# RP2040.net
KiCad netlist of a schematic drawn in Altium Designer
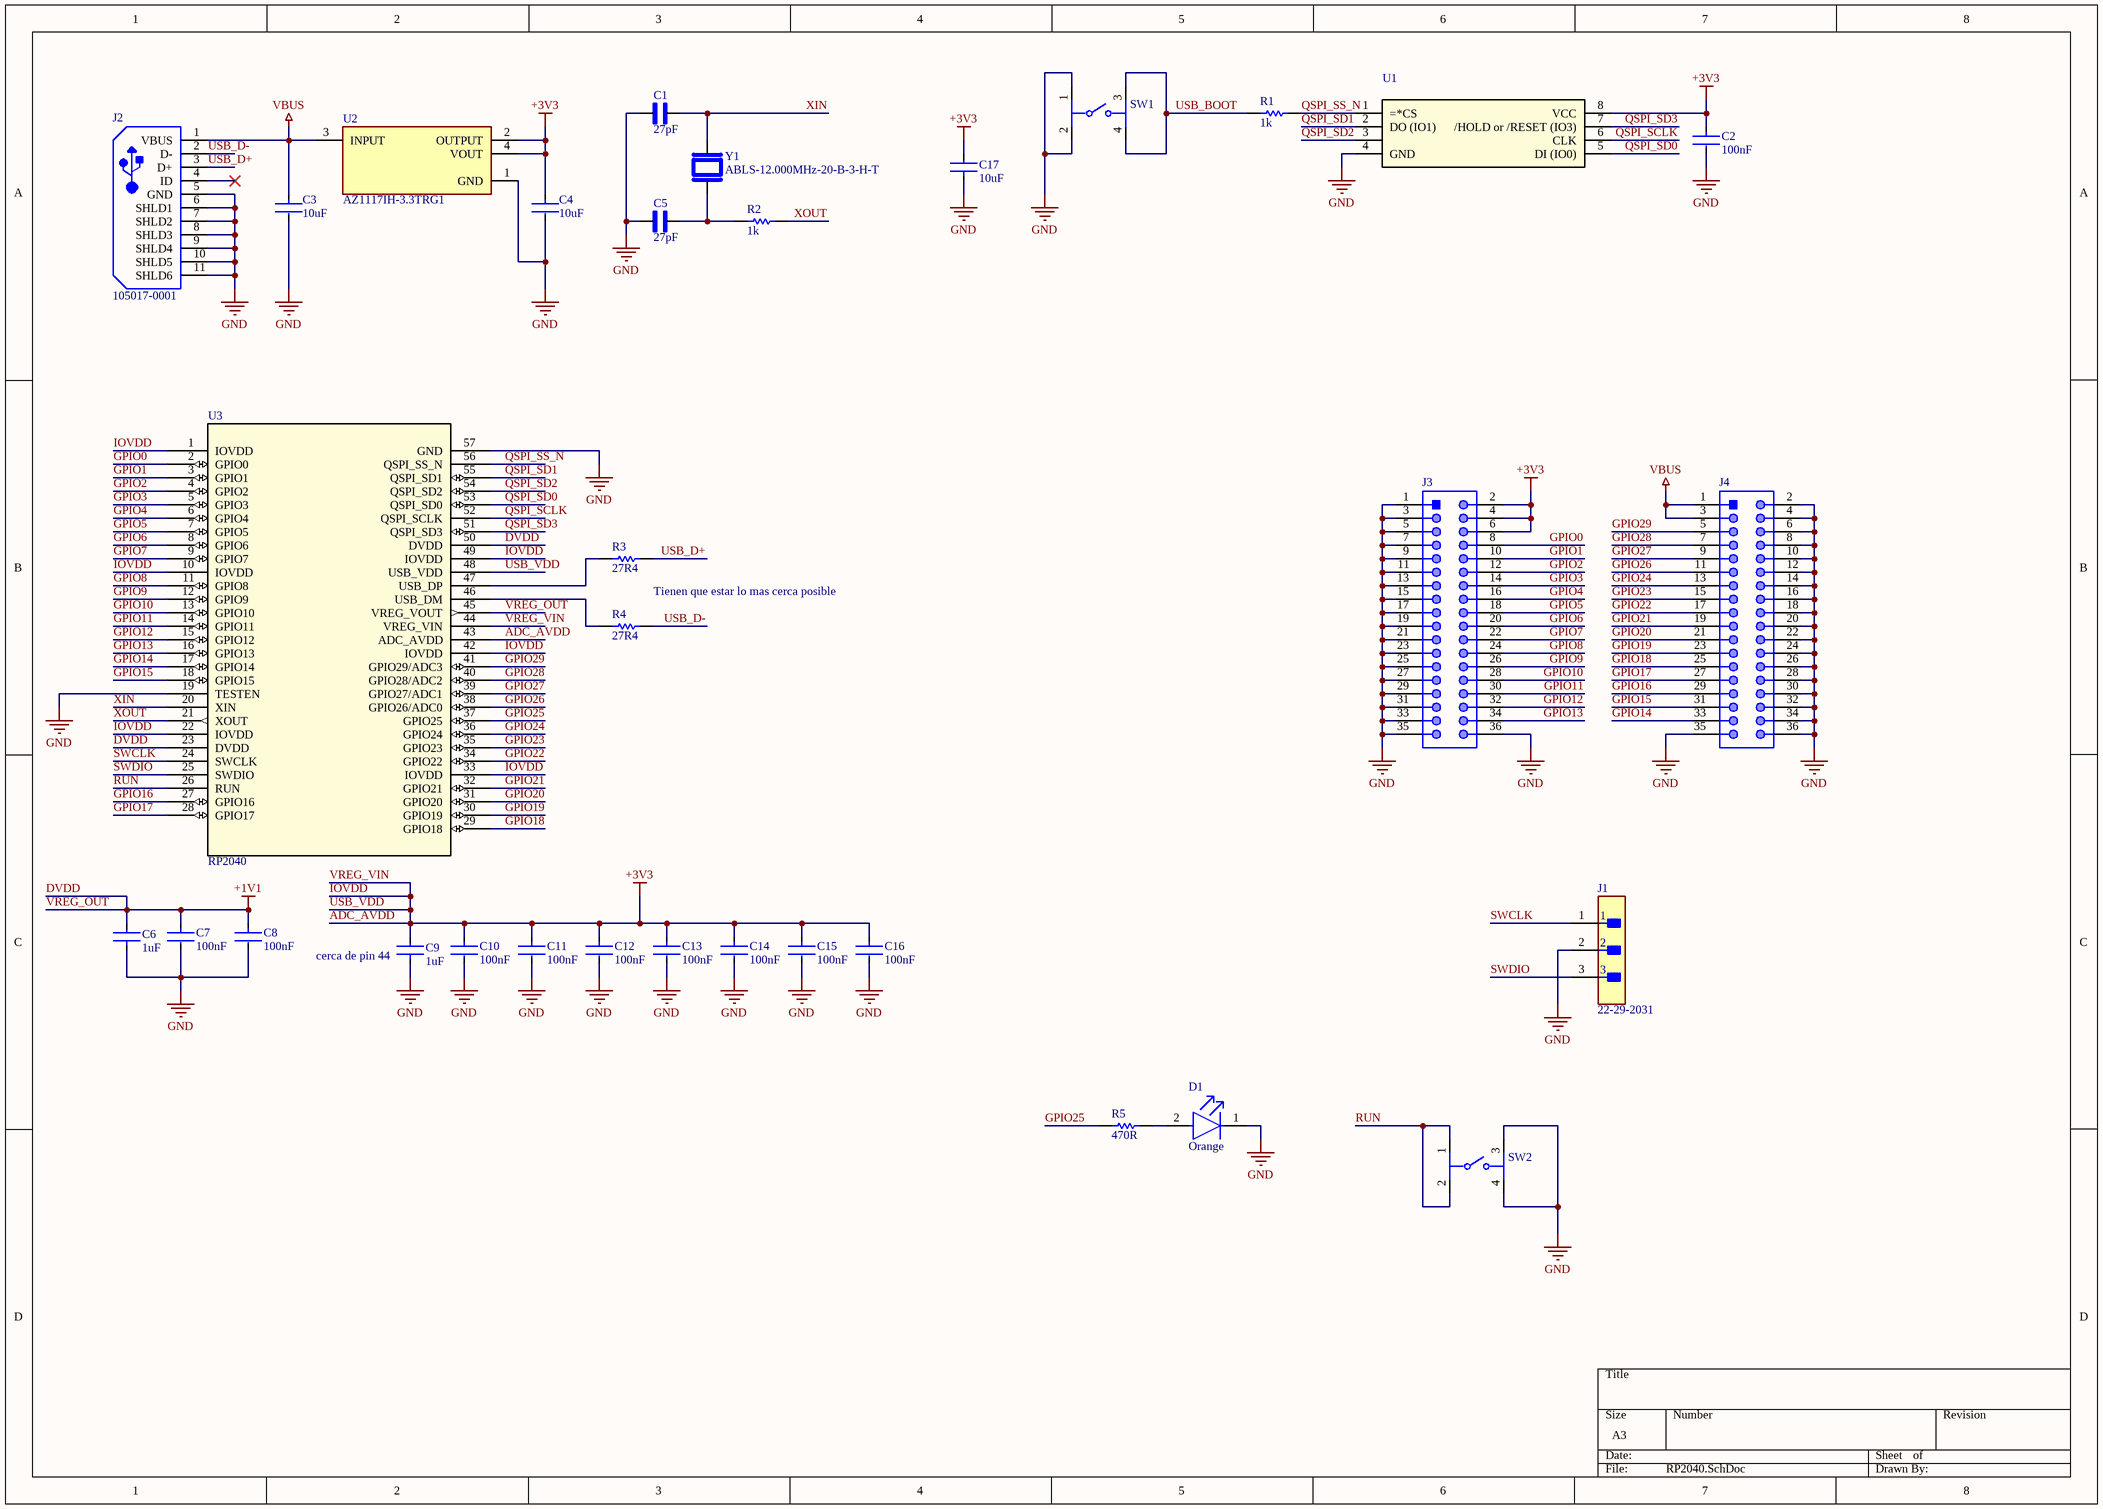
[diagram p0: RP2040.SchDoc]

(export (version "E")
  (design (tool "Eeschema 10.0.6"))
  (components
    (comp (ref "C1")
      (value "CL21C270JCANNNC")
      (footprint "CAPC2012X140N")
      (description "CL21 Series 27 pF 100 V ±5 % Tolerance C0G SMT Multilayer Ceramic Capacitor")
      (fields
        (field (name "MANUFACTURER") "Samsung")
        (field (name "TOLERANCE") "5%")
        (field (name "CAPACITANCE") "27pF")
      )
      (libsource (lib "CL21C270JCANNNC") (part "CL21C270JCANNNC"))
    )
    (comp (ref "C2")
      (value "CL21B104KBCNNNC")
      (footprint "FP-CL21-IPC_C")
      (description "CL21 Series 0805 100nF 50V ±10% Tolerance X7R Multilayer Ceramic Chip Capacitor")
      (fields
        (field (name "TOLERANCE") "10%")
        (field (name "CAPACITANCE") "100nF")
        (field (name "VOLTAGE") "50V")
      )
      (libsource (lib "Altium Content Vault") (part "b4654b650e69147ec39a6b967a45e02"))
    )
    (comp (ref "C3")
      (value "GRM21BR61C106KE15K")
      (footprint "FP-GRM21B-0_1-IPC_A")
      (description "Chip Multilayer Ceramic Capacitors for General Purpose, 0805, 10uF, X5R, 15%, 10%, 16V")
      (fields
        (field (name "TOLERANCE") "10%")
        (field (name "VOLTAGE") "16V")
        (field (name "CAPACITANCE") "10uF")
      )
      (libsource (lib "Altium Content Vault") (part "b4654b650e69147ec39a6b967a45e02"))
    )
    (comp (ref "C4")
      (value "GRM21BR61C106KE15K")
      (footprint "FP-GRM21B-0_1-IPC_A")
      (description "Chip Multilayer Ceramic Capacitors for General Purpose, 0805, 10uF, X5R, 15%, 10%, 16V")
      (fields
        (field (name "TOLERANCE") "10%")
        (field (name "VOLTAGE") "16V")
        (field (name "CAPACITANCE") "10uF")
      )
      (libsource (lib "Altium Content Vault") (part "b4654b650e69147ec39a6b967a45e02"))
    )
    (comp (ref "C5")
      (value "CL21C270JCANNNC")
      (footprint "CAPC2012X140N")
      (description "CL21 Series 27 pF 100 V ±5 % Tolerance C0G SMT Multilayer Ceramic Capacitor")
      (fields
        (field (name "MANUFACTURER") "Samsung")
        (field (name "TOLERANCE") "5%")
        (field (name "CAPACITANCE") "27pF")
      )
      (libsource (lib "CL21C270JCANNNC") (part "CL21C270JCANNNC"))
    )
    (comp (ref "C6")
      (value "CL21B105KOFNNNE")
      (footprint "FP-CL21-IPC_A")
      (description "CL21 Series 0805 1uF 16V ±10% Tolerance X7R Multilayer Ceramic Chip Capacitor")
      (fields
        (field (name "CAPACITANCE") "1uF")
        (field (name "TOLERANCE") "10%")
        (field (name "VOLTAGE") "16V")
      )
      (libsource (lib "Altium Content Vault") (part "b4654b650e69147ec39a6b967a45e02"))
    )
    (comp (ref "C7")
      (value "CL21B104KBCNNNC")
      (footprint "FP-CL21-IPC_A")
      (description "CL21 Series 0805 100nF 50V ±10% Tolerance X7R Multilayer Ceramic Chip Capacitor")
      (fields
        (field (name "TOLERANCE") "10%")
        (field (name "CAPACITANCE") "100nF")
        (field (name "VOLTAGE") "50V")
      )
      (libsource (lib "Altium Content Vault") (part "b4654b650e69147ec39a6b967a45e02"))
    )
    (comp (ref "C8")
      (value "CL21B104KBCNNNC")
      (footprint "FP-CL21-IPC_A")
      (description "CL21 Series 0805 100nF 50V ±10% Tolerance X7R Multilayer Ceramic Chip Capacitor")
      (fields
        (field (name "TOLERANCE") "10%")
        (field (name "CAPACITANCE") "100nF")
        (field (name "VOLTAGE") "50V")
      )
      (libsource (lib "Altium Content Vault") (part "b4654b650e69147ec39a6b967a45e02"))
    )
    (comp (ref "C9")
      (value "CL21B105KOFNNNE")
      (footprint "FP-CL21-IPC_A")
      (description "CL21 Series 0805 1uF 16V ±10% Tolerance X7R Multilayer Ceramic Chip Capacitor")
      (fields
        (field (name "CAPACITANCE") "1uF")
        (field (name "TOLERANCE") "10%")
        (field (name "VOLTAGE") "16V")
      )
      (libsource (lib "Altium Content Vault") (part "b4654b650e69147ec39a6b967a45e02"))
    )
    (comp (ref "C10")
      (value "CL21B104KBCNNNC")
      (footprint "FP-CL21-IPC_A")
      (description "CL21 Series 0805 100nF 50V ±10% Tolerance X7R Multilayer Ceramic Chip Capacitor")
      (fields
        (field (name "TOLERANCE") "10%")
        (field (name "CAPACITANCE") "100nF")
        (field (name "VOLTAGE") "50V")
      )
      (libsource (lib "Altium Content Vault") (part "b4654b650e69147ec39a6b967a45e02"))
    )
    (comp (ref "C11")
      (value "CL21B104KBCNNNC")
      (footprint "FP-CL21-IPC_A")
      (description "CL21 Series 0805 100nF 50V ±10% Tolerance X7R Multilayer Ceramic Chip Capacitor")
      (fields
        (field (name "TOLERANCE") "10%")
        (field (name "CAPACITANCE") "100nF")
        (field (name "VOLTAGE") "50V")
      )
      (libsource (lib "Altium Content Vault") (part "b4654b650e69147ec39a6b967a45e02"))
    )
    (comp (ref "C12")
      (value "CL21B104KBCNNNC")
      (footprint "FP-CL21-IPC_A")
      (description "CL21 Series 0805 100nF 50V ±10% Tolerance X7R Multilayer Ceramic Chip Capacitor")
      (fields
        (field (name "TOLERANCE") "10%")
        (field (name "CAPACITANCE") "100nF")
        (field (name "VOLTAGE") "50V")
      )
      (libsource (lib "Altium Content Vault") (part "b4654b650e69147ec39a6b967a45e02"))
    )
    (comp (ref "C13")
      (value "CL21B104KBCNNNC")
      (footprint "FP-CL21-IPC_A")
      (description "CL21 Series 0805 100nF 50V ±10% Tolerance X7R Multilayer Ceramic Chip Capacitor")
      (fields
        (field (name "TOLERANCE") "10%")
        (field (name "CAPACITANCE") "100nF")
        (field (name "VOLTAGE") "50V")
      )
      (libsource (lib "Altium Content Vault") (part "b4654b650e69147ec39a6b967a45e02"))
    )
    (comp (ref "C14")
      (value "CL21B104KBCNNNC")
      (footprint "FP-CL21-IPC_A")
      (description "CL21 Series 0805 100nF 50V ±10% Tolerance X7R Multilayer Ceramic Chip Capacitor")
      (fields
        (field (name "TOLERANCE") "10%")
        (field (name "CAPACITANCE") "100nF")
        (field (name "VOLTAGE") "50V")
      )
      (libsource (lib "Altium Content Vault") (part "b4654b650e69147ec39a6b967a45e02"))
    )
    (comp (ref "C15")
      (value "CL21B104KBCNNNC")
      (footprint "FP-CL21-IPC_A")
      (description "CL21 Series 0805 100nF 50V ±10% Tolerance X7R Multilayer Ceramic Chip Capacitor")
      (fields
        (field (name "TOLERANCE") "10%")
        (field (name "CAPACITANCE") "100nF")
        (field (name "VOLTAGE") "50V")
      )
      (libsource (lib "Altium Content Vault") (part "b4654b650e69147ec39a6b967a45e02"))
    )
    (comp (ref "C16")
      (value "CL21B104KBCNNNC")
      (footprint "FP-CL21-IPC_A")
      (description "CL21 Series 0805 100nF 50V ±10% Tolerance X7R Multilayer Ceramic Chip Capacitor")
      (fields
        (field (name "TOLERANCE") "10%")
        (field (name "CAPACITANCE") "100nF")
        (field (name "VOLTAGE") "50V")
      )
      (libsource (lib "Altium Content Vault") (part "b4654b650e69147ec39a6b967a45e02"))
    )
    (comp (ref "C17")
      (value "GRM21BR61C106KE15K")
      (footprint "FP-GRM21B-0_1-IPC_A")
      (description "Chip Multilayer Ceramic Capacitors for General Purpose, 0805, 10uF, X5R, 15%, 10%, 16V")
      (fields
        (field (name "TOLERANCE") "10%")
        (field (name "VOLTAGE") "16V")
        (field (name "CAPACITANCE") "10uF")
      )
      (libsource (lib "Altium Content Vault") (part "b4654b650e69147ec39a6b967a45e02"))
    )
    (comp (ref "D1")
      (value "APTR3216SECK")
      (footprint "FP-APTR3216SECK-MFG")
      (description "LED ORANGE CLEAR CHIP SMD")
      (fields (field (name "ILLUMINATION COLOR") "Orange") (field (name "MANUFACTURER") "Kingbright"))
      (libsource (lib "Altium Content Vault") (part "8706943c75ba83719d021d2fdc84c58"))
    )
    (comp (ref "J1")
      (value "22-29-2031")
      (footprint "FP-22-29-2031-MFG")
      (description "CONN HEADER VERT 3POS 2.54MM")
      (libsource (lib "Altium Content Vault") (part "0d3f023dd272f625e17a2be33dea85f"))
    )
    (comp (ref "J2")
      (value "105017-0001")
      (footprint "USB-MICRO-B_V")
      (fields (field (name "MANUFACTURER") "Molex") (field (name "MANUFACTURER PART NUMBER") "1050170001"))
      (libsource (lib "Altium Content Vault") (part "USB-5-6SHLD"))
    )
    (comp (ref "J3")
      (value "61303621121")
      (footprint "61303621121")
      (description "THT Vertical Pin Header WR-PHD, Pitch 2.54 mm, Dual Row, 36 pins")
      (fields (field (name "MANUFACTURER") "Wurth Elektronik") (field (name "PUBLISHER") "WurthElektronik"))
      (libsource (lib "Altium Content Vault") (part "WE-CN-2P-M-R36"))
    )
    (comp (ref "J4")
      (value "61303621121")
      (footprint "61303621121")
      (description "THT Vertical Pin Header WR-PHD, Pitch 2.54 mm, Dual Row, 36 pins")
      (fields (field (name "MANUFACTURER") "Wurth Elektronik") (field (name "PUBLISHER") "WurthElektronik"))
      (libsource (lib "Altium Content Vault") (part "WE-CN-2P-M-R36"))
    )
    (comp (ref "R1")
      (value "RC0805JR-131KL")
      (footprint "RESC2013X60X35ML10T20")
      (description "Res Thick Film 0805 1K Ohm 5% 0.125W(1/8W) ±100ppm/C Pad SMD T/R")
      (fields
        (field (name "MANUFACTURER") "Yageo")
        (field (name "RESISTANCE") "1k")
        (field (name "TOLERANCE") "5%")
      )
      (libsource (lib "Altium Content Vault") (part "RES"))
    )
    (comp (ref "R2")
      (value "RC0805JR-131KL")
      (footprint "RESC2013X60X35ML10T20")
      (fields
        (field (name "MANUFACTURER") "Yageo")
        (field (name "RESISTANCE") "1k")
        (field (name "TOLERANCE") "5%")
      )
      (libsource (lib "Altium Content Vault") (part "RES"))
    )
    (comp (ref "R3")
      (value "RK73H2ATTD27R4F")
      (footprint "RESC2013X60X30NL20T20")
      (description "Res Thick Film 0805 27.4 Ohm 1% 0.25W(1/4W) ±100ppm/C Pad SMD Automotive T/R")
      (fields
        (field (name "MANUFACTURER") "KOA Speer")
        (field (name "RESISTANCE") "27R4")
        (field (name "TOLERANCE") "1%")
      )
      (libsource (lib "Altium Content Vault") (part "RES"))
    )
    (comp (ref "R4")
      (value "RK73H2ATTD27R4F")
      (footprint "RESC2013X60X30NL20T20")
      (description "Res Thick Film 0805 27.4 Ohm 1% 0.25W(1/4W) ±100ppm/C Pad SMD Automotive T/R")
      (fields
        (field (name "MANUFACTURER") "KOA Speer")
        (field (name "RESISTANCE") "27R4")
        (field (name "TOLERANCE") "1%")
      )
      (libsource (lib "Altium Content Vault") (part "RES"))
    )
    (comp (ref "R5")
      (value "RC0805FR-07470RL")
      (footprint "RESC2013X60X35LL10T20")
      (description "Chip Resistor, 470 Ohm, +/- 1%, 125 mW, -55 to 155 degC, 0805 (2012 Metric), RoHS, Tape and Reel")
      (fields
        (field (name "MANUFACTURER") "Yageo")
        (field (name "RESISTANCE") "470R")
        (field (name "TOLERANCE") "1%")
      )
      (libsource (lib "Altium Content Vault") (part "RES-2"))
    )
    (comp (ref "SW1")
      (value "PTS526SK15SMTR2LFS")
      (footprint "FP-PTS526SK15SMTR2LFS-MFG")
      (description "TACT 5.2 X 5.2, 1.5 MM H, 260GF,")
      (fields
        (field (name "MANUFACTURER") "C&K")
        (field (name "OCTOPART") "https://octopart.com/pts526+sk15+smtr2+lfs-c%26k+components-100617999")
      )
      (libsource (lib "Altium Content Vault") (part "b8895f3f4cefb76e1819d2863dba89b"))
    )
    (comp (ref "SW2")
      (value "PTS526SK15SMTR2LFS")
      (footprint "FP-PTS526SK15SMTR2LFS-MFG")
      (description "TACT 5.2 X 5.2, 1.5 MM H, 260GF,")
      (fields
        (field (name "MANUFACTURER") "C&K")
        (field (name "OCTOPART") "https://octopart.com/pts526+sk15+smtr2+lfs-c%26k+components-100617999")
      )
      (libsource (lib "Altium Content Vault") (part "b8895f3f4cefb76e1819d2863dba89b"))
    )
    (comp (ref "U1")
      (value "W25Q128JVSIQ")
      (footprint "W25Q128JVSIQ")
      (description "NOR Flash Serial (SPI, Dual SPI, Quad SPI) 3.3V 128M-bit 16M x 8 6ns 8-Pin SOIC Tube")
      (fields
        (field (name "MANUFACTURER") "Winbond")
        (field (name "COPYRIGHT") "Copyright (C) 2022 Ultra Librarian. All rights reserved.")
      )
      (libsource (lib "W25Q128JVSIQ") (part "W25Q128JVSIQ"))
    )
    (comp (ref "U2")
      (value "AZ1117IH-3.3TRG1")
      (footprint "FP-SOT223-IPC_B")
      (description "Linear Voltage Regulator IC Positive Fixed 1 Output 3.3V 800mA SOT-223")
      (fields (field (name "MANUFACTURER") "Diodes"))
      (libsource (lib "Altium Content Vault") (part "3c8a0cc3f7d1fafcf032f21e1bb5f65"))
    )
    (comp (ref "U3")
      (value "RP2040")
      (footprint "RP2040")
      (description "ARM® Cortex®-M0+ - Microcontroller IC 32-Bit Dual-Core 133MHz External Program Memory 56-QFN (7x7)")
      (fields
        (field (name "MANUFACTURER") "Raspberry Pi")
        (field (name "MANUFACTURER PART NUMBER") "SC0914(13)")
      )
      (libsource (lib "RP2040") (part "RP2040"))
    )
    (comp (ref "Y1")
      (value "ABLS-12.000MHz-20-B-3-H-T")
      (footprint "XTAL_ABLS-12.000MHz-20-B-3-H-T")
      (description "Crystal 12MHz ±25ppm (Tol) ±35ppm (Stability) 20pF FUND 50Ohm 2-Pin HC-49/US SMD T/R")
      (fields (field (name "MF") "Abracon LLC") (field (name "DIGI-KEY_PART_NUMBER") "535-15006-2-ND"))
      (libsource (lib "ABLS-12.000MHz-20-B-3-H-T") (part "ABLS-12.000MHz-20-B-3-H-T"))
    )
  )
  (nets
    (net (code "1") (name "+1V1") (class "Default")
      (node (ref "C6") (pin "2") (pinfunction "2_2") (pintype "passive"))
      (node (ref "C7") (pin "1") (pinfunction "1_1") (pintype "passive"))
      (node (ref "C8") (pin "1") (pinfunction "1_1") (pintype "passive"))
      (node (ref "U3") (pin "23") (pinfunction "DVDD_23") (pintype "power_in"))
      (node (ref "U3") (pin "45") (pinfunction "VREG_VOUT_45") (pintype "output"))
      (node (ref "U3") (pin "50") (pinfunction "DVDD_50") (pintype "power_in"))
    )
    (net (code "2") (name "+3V3") (class "Default")
      (node (ref "C10") (pin "1") (pinfunction "1_1") (pintype "passive"))
      (node (ref "C11") (pin "1") (pinfunction "1_1") (pintype "passive"))
      (node (ref "C12") (pin "1") (pinfunction "1_1") (pintype "passive"))
      (node (ref "C13") (pin "1") (pinfunction "1_1") (pintype "passive"))
      (node (ref "C14") (pin "1") (pinfunction "1_1") (pintype "passive"))
      (node (ref "C15") (pin "1") (pinfunction "1_1") (pintype "passive"))
      (node (ref "C16") (pin "1") (pinfunction "1_1") (pintype "passive"))
      (node (ref "C17") (pin "2") (pinfunction "2_2") (pintype "passive"))
      (node (ref "C2") (pin "1") (pinfunction "1_1") (pintype "passive"))
      (node (ref "C4") (pin "1") (pinfunction "1_1") (pintype "passive"))
      (node (ref "C9") (pin "2") (pinfunction "2_2") (pintype "passive"))
      (node (ref "J3") (pin "2") (pinfunction "2_2") (pintype "passive"))
      (node (ref "J3") (pin "4") (pinfunction "4_4") (pintype "passive"))
      (node (ref "J3") (pin "6") (pinfunction "6_6") (pintype "passive"))
      (node (ref "U1") (pin "8") (pinfunction "VCC_8") (pintype "power_in"))
      (node (ref "U2") (pin "2") (pinfunction "OUTPUT_2") (pintype "power_in"))
      (node (ref "U2") (pin "4") (pinfunction "VOUT_4") (pintype "power_in"))
      (node (ref "U3") (pin "1") (pinfunction "IOVDD_1") (pintype "power_in"))
      (node (ref "U3") (pin "10") (pinfunction "IOVDD_10") (pintype "power_in"))
      (node (ref "U3") (pin "22") (pinfunction "IOVDD_22") (pintype "power_in"))
      (node (ref "U3") (pin "33") (pinfunction "IOVDD_33") (pintype "power_in"))
      (node (ref "U3") (pin "42") (pinfunction "IOVDD_42") (pintype "power_in"))
      (node (ref "U3") (pin "43") (pinfunction "ADC_AVDD_43") (pintype "power_in"))
      (node (ref "U3") (pin "44") (pinfunction "VREG_VIN_44") (pintype "passive"))
      (node (ref "U3") (pin "48") (pinfunction "USB_VDD_48") (pintype "power_in"))
      (node (ref "U3") (pin "49") (pinfunction "IOVDD_49") (pintype "power_in"))
    )
    (net (code "3") (name "/GPIO0") (class "Default")
      (node (ref "J3") (pin "8") (pinfunction "8_8") (pintype "passive"))
      (node (ref "U3") (pin "2") (pinfunction "GPIO0_2") (pintype "bidirectional"))
    )
    (net (code "4") (name "/GPIO1") (class "Default")
      (node (ref "J3") (pin "10") (pinfunction "10_10") (pintype "passive"))
      (node (ref "U3") (pin "3") (pinfunction "GPIO1_3") (pintype "bidirectional"))
    )
    (net (code "5") (name "/GPIO2") (class "Default")
      (node (ref "J3") (pin "12") (pinfunction "12_12") (pintype "passive"))
      (node (ref "U3") (pin "4") (pinfunction "GPIO2_4") (pintype "bidirectional"))
    )
    (net (code "6") (name "/GPIO3") (class "Default")
      (node (ref "J3") (pin "14") (pinfunction "14_14") (pintype "passive"))
      (node (ref "U3") (pin "5") (pinfunction "GPIO3_5") (pintype "bidirectional"))
    )
    (net (code "7") (name "/GPIO4") (class "Default")
      (node (ref "J3") (pin "16") (pinfunction "16_16") (pintype "passive"))
      (node (ref "U3") (pin "6") (pinfunction "GPIO4_6") (pintype "bidirectional"))
    )
    (net (code "8") (name "/GPIO5") (class "Default")
      (node (ref "J3") (pin "18") (pinfunction "18_18") (pintype "passive"))
      (node (ref "U3") (pin "7") (pinfunction "GPIO5_7") (pintype "bidirectional"))
    )
    (net (code "9") (name "/GPIO6") (class "Default")
      (node (ref "J3") (pin "20") (pinfunction "20_20") (pintype "passive"))
      (node (ref "U3") (pin "8") (pinfunction "GPIO6_8") (pintype "bidirectional"))
    )
    (net (code "10") (name "/GPIO7") (class "Default")
      (node (ref "J3") (pin "22") (pinfunction "22_22") (pintype "passive"))
      (node (ref "U3") (pin "9") (pinfunction "GPIO7_9") (pintype "bidirectional"))
    )
    (net (code "11") (name "/GPIO8") (class "Default")
      (node (ref "J3") (pin "24") (pinfunction "24_24") (pintype "passive"))
      (node (ref "U3") (pin "11") (pinfunction "GPIO8_11") (pintype "bidirectional"))
    )
    (net (code "12") (name "/GPIO9") (class "Default")
      (node (ref "J3") (pin "26") (pinfunction "26_26") (pintype "passive"))
      (node (ref "U3") (pin "12") (pinfunction "GPIO9_12") (pintype "bidirectional"))
    )
    (net (code "13") (name "/GPIO10") (class "Default")
      (node (ref "J3") (pin "28") (pinfunction "28_28") (pintype "passive"))
      (node (ref "U3") (pin "13") (pinfunction "GPIO10_13") (pintype "bidirectional"))
    )
    (net (code "14") (name "/GPIO11") (class "Default")
      (node (ref "J3") (pin "30") (pinfunction "30_30") (pintype "passive"))
      (node (ref "U3") (pin "14") (pinfunction "GPIO11_14") (pintype "bidirectional"))
    )
    (net (code "15") (name "/GPIO12") (class "Default")
      (node (ref "J3") (pin "32") (pinfunction "32_32") (pintype "passive"))
      (node (ref "U3") (pin "15") (pinfunction "GPIO12_15") (pintype "bidirectional"))
    )
    (net (code "16") (name "/GPIO13") (class "Default")
      (node (ref "J3") (pin "34") (pinfunction "34_34") (pintype "passive"))
      (node (ref "U3") (pin "16") (pinfunction "GPIO13_16") (pintype "bidirectional"))
    )
    (net (code "17") (name "/GPIO14") (class "Default")
      (node (ref "J4") (pin "33") (pinfunction "33_33") (pintype "passive"))
      (node (ref "U3") (pin "17") (pinfunction "GPIO14_17") (pintype "bidirectional"))
    )
    (net (code "18") (name "/GPIO15") (class "Default")
      (node (ref "J4") (pin "31") (pinfunction "31_31") (pintype "passive"))
      (node (ref "U3") (pin "18") (pinfunction "GPIO15_18") (pintype "bidirectional"))
    )
    (net (code "19") (name "/GPIO16") (class "Default")
      (node (ref "J4") (pin "29") (pinfunction "29_29") (pintype "passive"))
      (node (ref "U3") (pin "27") (pinfunction "GPIO16_27") (pintype "bidirectional"))
    )
    (net (code "20") (name "/GPIO17") (class "Default")
      (node (ref "J4") (pin "27") (pinfunction "27_27") (pintype "passive"))
      (node (ref "U3") (pin "28") (pinfunction "GPIO17_28") (pintype "bidirectional"))
    )
    (net (code "21") (name "/GPIO18") (class "Default")
      (node (ref "J4") (pin "25") (pinfunction "25_25") (pintype "passive"))
      (node (ref "U3") (pin "29") (pinfunction "GPIO18_29") (pintype "bidirectional"))
    )
    (net (code "22") (name "/GPIO19") (class "Default")
      (node (ref "J4") (pin "23") (pinfunction "23_23") (pintype "passive"))
      (node (ref "U3") (pin "30") (pinfunction "GPIO19_30") (pintype "bidirectional"))
    )
    (net (code "23") (name "/GPIO20") (class "Default")
      (node (ref "J4") (pin "21") (pinfunction "21_21") (pintype "passive"))
      (node (ref "U3") (pin "31") (pinfunction "GPIO20_31") (pintype "bidirectional"))
    )
    (net (code "24") (name "/GPIO21") (class "Default")
      (node (ref "J4") (pin "19") (pinfunction "19_19") (pintype "passive"))
      (node (ref "U3") (pin "32") (pinfunction "GPIO21_32") (pintype "bidirectional"))
    )
    (net (code "25") (name "/GPIO22") (class "Default")
      (node (ref "J4") (pin "17") (pinfunction "17_17") (pintype "passive"))
      (node (ref "U3") (pin "34") (pinfunction "GPIO22_34") (pintype "bidirectional"))
    )
    (net (code "26") (name "/GPIO23") (class "Default")
      (node (ref "J4") (pin "15") (pinfunction "15_15") (pintype "passive"))
      (node (ref "U3") (pin "35") (pinfunction "GPIO23_35") (pintype "bidirectional"))
    )
    (net (code "27") (name "/GPIO24") (class "Default")
      (node (ref "J4") (pin "13") (pinfunction "13_13") (pintype "passive"))
      (node (ref "U3") (pin "36") (pinfunction "GPIO24_36") (pintype "bidirectional"))
    )
    (net (code "28") (name "/GPIO25") (class "Default")
      (node (ref "R5") (pin "1") (pinfunction "1_1") (pintype "passive"))
      (node (ref "U3") (pin "37") (pinfunction "GPIO25_37") (pintype "bidirectional"))
    )
    (net (code "29") (name "/GPIO26") (class "Default")
      (node (ref "J4") (pin "11") (pinfunction "11_11") (pintype "passive"))
      (node (ref "U3") (pin "38") (pinfunction "GPIO26/ADC0_38") (pintype "bidirectional"))
    )
    (net (code "30") (name "/GPIO27") (class "Default")
      (node (ref "J4") (pin "9") (pinfunction "9_9") (pintype "passive"))
      (node (ref "U3") (pin "39") (pinfunction "GPIO27/ADC1_39") (pintype "bidirectional"))
    )
    (net (code "31") (name "/GPIO28") (class "Default")
      (node (ref "J4") (pin "7") (pinfunction "7_7") (pintype "passive"))
      (node (ref "U3") (pin "40") (pinfunction "GPIO28/ADC2_40") (pintype "bidirectional"))
    )
    (net (code "32") (name "/GPIO29") (class "Default")
      (node (ref "J4") (pin "5") (pinfunction "5_5") (pintype "passive"))
      (node (ref "U3") (pin "41") (pinfunction "GPIO29/ADC3_41") (pintype "bidirectional"))
    )
    (net (code "33") (name "/QSPI_SCLK") (class "Default")
      (node (ref "U1") (pin "6") (pinfunction "CLK_6") (pintype "passive"))
      (node (ref "U3") (pin "52") (pinfunction "QSPI_SCLK_52") (pintype "passive"))
    )
    (net (code "34") (name "/QSPI_SD0") (class "Default")
      (node (ref "U1") (pin "5") (pinfunction "DI_(IO0)_5") (pintype "passive"))
      (node (ref "U3") (pin "53") (pinfunction "QSPI_SD0_53") (pintype "bidirectional"))
    )
    (net (code "35") (name "/QSPI_SD1") (class "Default")
      (node (ref "U1") (pin "2") (pinfunction "DO_(IO1)_2") (pintype "passive"))
      (node (ref "U3") (pin "55") (pinfunction "QSPI_SD1_55") (pintype "bidirectional"))
    )
    (net (code "36") (name "/QSPI_SD2") (class "Default")
      (node (ref "U1") (pin "3") (pinfunction "/WP_(IO2)_3") (pintype "passive"))
      (node (ref "U3") (pin "54") (pinfunction "QSPI_SD2_54") (pintype "bidirectional"))
    )
    (net (code "37") (name "/QSPI_SD3") (class "Default")
      (node (ref "U1") (pin "7") (pinfunction "/HOLD_or_/RESET_(IO3)_7") (pintype "passive"))
      (node (ref "U3") (pin "51") (pinfunction "QSPI_SD3_51") (pintype "bidirectional"))
    )
    (net (code "38") (name "/QSPI_SS_N") (class "Default")
      (node (ref "R1") (pin "1") (pinfunction "1_1") (pintype "passive"))
      (node (ref "U1") (pin "1") (pinfunction "=*CS_1") (pintype "passive"))
      (node (ref "U3") (pin "56") (pinfunction "QSPI_SS_N_56") (pintype "passive"))
    )
    (net (code "39") (name "/RUN") (class "Default")
      (node (ref "SW2") (pin "1") (pinfunction "1_1") (pintype "passive"))
      (node (ref "SW2") (pin "2") (pinfunction "2_2") (pintype "passive"))
      (node (ref "U3") (pin "26") (pinfunction "RUN_26") (pintype "passive"))
    )
    (net (code "40") (name "/SWCLK") (class "Default")
      (node (ref "J1") (pin "1") (pinfunction "1_1") (pintype "passive"))
      (node (ref "U3") (pin "24") (pinfunction "SWCLK_24") (pintype "passive"))
    )
    (net (code "41") (name "/SWDIO") (class "Default")
      (node (ref "J1") (pin "3") (pinfunction "3_3") (pintype "passive"))
      (node (ref "U3") (pin "25") (pinfunction "SWDIO_25") (pintype "passive"))
    )
    (net (code "42") (name "/USB_BOOT") (class "Default")
      (node (ref "R1") (pin "2") (pinfunction "2_2") (pintype "passive"))
      (node (ref "SW1") (pin "3") (pinfunction "3_3") (pintype "passive"))
      (node (ref "SW1") (pin "4") (pinfunction "4_4") (pintype "passive"))
    )
    (net (code "43") (name "/USB_D+") (class "Default")
      (node (ref "J2") (pin "3") (pinfunction "D+_3") (pintype "passive"))
      (node (ref "R3") (pin "1") (pinfunction "1_1") (pintype "passive"))
    )
    (net (code "44") (name "/USB_D-") (class "Default")
      (node (ref "J2") (pin "2") (pinfunction "D-_2") (pintype "passive"))
      (node (ref "R4") (pin "1") (pinfunction "1_1") (pintype "passive"))
    )
    (net (code "45") (name "/XIN") (class "Default")
      (node (ref "C1") (pin "1") (pinfunction "1_1") (pintype "passive"))
      (node (ref "U3") (pin "20") (pinfunction "XIN_20") (pintype "passive"))
      (node (ref "Y1") (pin "2") (pinfunction "2_2") (pintype "passive"))
    )
    (net (code "46") (name "/XOUT") (class "Default")
      (node (ref "R2") (pin "1") (pinfunction "1_1") (pintype "passive"))
      (node (ref "U3") (pin "21") (pinfunction "XOUT_21") (pintype "output"))
    )
    (net (code "47") (name "GND") (class "Default")
      (node (ref "C1") (pin "2") (pinfunction "2_2") (pintype "passive"))
      (node (ref "C10") (pin "2") (pinfunction "2_2") (pintype "passive"))
      (node (ref "C11") (pin "2") (pinfunction "2_2") (pintype "passive"))
      (node (ref "C12") (pin "2") (pinfunction "2_2") (pintype "passive"))
      (node (ref "C13") (pin "2") (pinfunction "2_2") (pintype "passive"))
      (node (ref "C14") (pin "2") (pinfunction "2_2") (pintype "passive"))
      (node (ref "C15") (pin "2") (pinfunction "2_2") (pintype "passive"))
      (node (ref "C16") (pin "2") (pinfunction "2_2") (pintype "passive"))
      (node (ref "C17") (pin "1") (pinfunction "1_1") (pintype "passive"))
      (node (ref "C2") (pin "2") (pinfunction "2_2") (pintype "passive"))
      (node (ref "C3") (pin "2") (pinfunction "2_2") (pintype "passive"))
      (node (ref "C4") (pin "2") (pinfunction "2_2") (pintype "passive"))
      (node (ref "C5") (pin "2") (pinfunction "2_2") (pintype "passive"))
      (node (ref "C6") (pin "1") (pinfunction "1_1") (pintype "passive"))
      (node (ref "C7") (pin "2") (pinfunction "2_2") (pintype "passive"))
      (node (ref "C8") (pin "2") (pinfunction "2_2") (pintype "passive"))
      (node (ref "C9") (pin "1") (pinfunction "1_1") (pintype "passive"))
      (node (ref "D1") (pin "1") (pinfunction "C_1") (pintype "passive"))
      (node (ref "J1") (pin "2") (pinfunction "2_2") (pintype "passive"))
      (node (ref "J2") (pin "10") (pinfunction "SHLD5_10") (pintype "passive"))
      (node (ref "J2") (pin "11") (pinfunction "SHLD6_11") (pintype "passive"))
      (node (ref "J2") (pin "5") (pinfunction "GND_5") (pintype "passive"))
      (node (ref "J2") (pin "6") (pinfunction "SHLD1_6") (pintype "passive"))
      (node (ref "J2") (pin "7") (pinfunction "SHLD2_7") (pintype "passive"))
      (node (ref "J2") (pin "8") (pinfunction "SHLD3_8") (pintype "passive"))
      (node (ref "J2") (pin "9") (pinfunction "SHLD4_9") (pintype "passive"))
      (node (ref "J3") (pin "1") (pinfunction "1_1") (pintype "passive"))
      (node (ref "J3") (pin "11") (pinfunction "11_11") (pintype "passive"))
      (node (ref "J3") (pin "13") (pinfunction "13_13") (pintype "passive"))
      (node (ref "J3") (pin "15") (pinfunction "15_15") (pintype "passive"))
      (node (ref "J3") (pin "17") (pinfunction "17_17") (pintype "passive"))
      (node (ref "J3") (pin "19") (pinfunction "19_19") (pintype "passive"))
      (node (ref "J3") (pin "21") (pinfunction "21_21") (pintype "passive"))
      (node (ref "J3") (pin "23") (pinfunction "23_23") (pintype "passive"))
      (node (ref "J3") (pin "25") (pinfunction "25_25") (pintype "passive"))
      (node (ref "J3") (pin "27") (pinfunction "27_27") (pintype "passive"))
      (node (ref "J3") (pin "29") (pinfunction "29_29") (pintype "passive"))
      (node (ref "J3") (pin "3") (pinfunction "3_3") (pintype "passive"))
      (node (ref "J3") (pin "31") (pinfunction "31_31") (pintype "passive"))
      (node (ref "J3") (pin "33") (pinfunction "33_33") (pintype "passive"))
      (node (ref "J3") (pin "35") (pinfunction "35_35") (pintype "passive"))
      (node (ref "J3") (pin "36") (pinfunction "36_36") (pintype "passive"))
      (node (ref "J3") (pin "5") (pinfunction "5_5") (pintype "passive"))
      (node (ref "J3") (pin "7") (pinfunction "7_7") (pintype "passive"))
      (node (ref "J3") (pin "9") (pinfunction "9_9") (pintype "passive"))
      (node (ref "J4") (pin "10") (pinfunction "10_10") (pintype "passive"))
      (node (ref "J4") (pin "12") (pinfunction "12_12") (pintype "passive"))
      (node (ref "J4") (pin "14") (pinfunction "14_14") (pintype "passive"))
      (node (ref "J4") (pin "16") (pinfunction "16_16") (pintype "passive"))
      (node (ref "J4") (pin "18") (pinfunction "18_18") (pintype "passive"))
      (node (ref "J4") (pin "2") (pinfunction "2_2") (pintype "passive"))
      (node (ref "J4") (pin "20") (pinfunction "20_20") (pintype "passive"))
      (node (ref "J4") (pin "22") (pinfunction "22_22") (pintype "passive"))
      (node (ref "J4") (pin "24") (pinfunction "24_24") (pintype "passive"))
      (node (ref "J4") (pin "26") (pinfunction "26_26") (pintype "passive"))
      (node (ref "J4") (pin "28") (pinfunction "28_28") (pintype "passive"))
      (node (ref "J4") (pin "30") (pinfunction "30_30") (pintype "passive"))
      (node (ref "J4") (pin "32") (pinfunction "32_32") (pintype "passive"))
      (node (ref "J4") (pin "34") (pinfunction "34_34") (pintype "passive"))
      (node (ref "J4") (pin "35") (pinfunction "35_35") (pintype "passive"))
      (node (ref "J4") (pin "36") (pinfunction "36_36") (pintype "passive"))
      (node (ref "J4") (pin "4") (pinfunction "4_4") (pintype "passive"))
      (node (ref "J4") (pin "6") (pinfunction "6_6") (pintype "passive"))
      (node (ref "J4") (pin "8") (pinfunction "8_8") (pintype "passive"))
      (node (ref "SW1") (pin "1") (pinfunction "1_1") (pintype "passive"))
      (node (ref "SW1") (pin "2") (pinfunction "2_2") (pintype "passive"))
      (node (ref "SW2") (pin "3") (pinfunction "3_3") (pintype "passive"))
      (node (ref "SW2") (pin "4") (pinfunction "4_4") (pintype "passive"))
      (node (ref "U1") (pin "4") (pinfunction "GND_4") (pintype "passive"))
      (node (ref "U2") (pin "1") (pinfunction "GND_1") (pintype "power_in"))
      (node (ref "U3") (pin "19") (pinfunction "TESTEN_19") (pintype "passive"))
      (node (ref "U3") (pin "57") (pinfunction "GND_57") (pintype "passive"))
    )
    (net (code "48") (name "Net-(C5-Pad1)") (class "Default")
      (node (ref "C5") (pin "1") (pinfunction "1_1") (pintype "passive"))
      (node (ref "R2") (pin "2") (pinfunction "2_2") (pintype "passive"))
      (node (ref "Y1") (pin "1") (pinfunction "1_1") (pintype "passive"))
    )
    (net (code "49") (name "Net-(D1-A)") (class "Default")
      (node (ref "D1") (pin "2") (pinfunction "A_2") (pintype "passive"))
      (node (ref "R5") (pin "2") (pinfunction "2_2") (pintype "passive"))
    )
    (net (code "50") (name "Net-(U3-USB_DM)") (class "Default")
      (node (ref "R4") (pin "2") (pinfunction "2_2") (pintype "passive"))
      (node (ref "U3") (pin "46") (pinfunction "USB_DM_46") (pintype "passive"))
    )
    (net (code "51") (name "Net-(U3-USB_DP)") (class "Default")
      (node (ref "R3") (pin "2") (pinfunction "2_2") (pintype "passive"))
      (node (ref "U3") (pin "47") (pinfunction "USB_DP_47") (pintype "passive"))
    )
    (net (code "52") (name "VBUS") (class "Default")
      (node (ref "C3") (pin "1") (pinfunction "1_1") (pintype "passive"))
      (node (ref "J2") (pin "1") (pinfunction "VBUS_1") (pintype "passive"))
      (node (ref "J4") (pin "1") (pinfunction "1_1") (pintype "passive"))
      (node (ref "J4") (pin "3") (pinfunction "3_3") (pintype "passive"))
      (node (ref "U2") (pin "3") (pinfunction "INPUT_3") (pintype "power_in"))
    )
    (net (code "53") (name "unconnected-(J2-ID-Pad4)") (class "Default")
      (node (ref "J2") (pin "4") (pinfunction "ID_4") (pintype "passive+no_connect"))
    )
  )
)
